# PIRI-MS-S2M.net
KiCad netlist of a schematic drawn in EAGLE
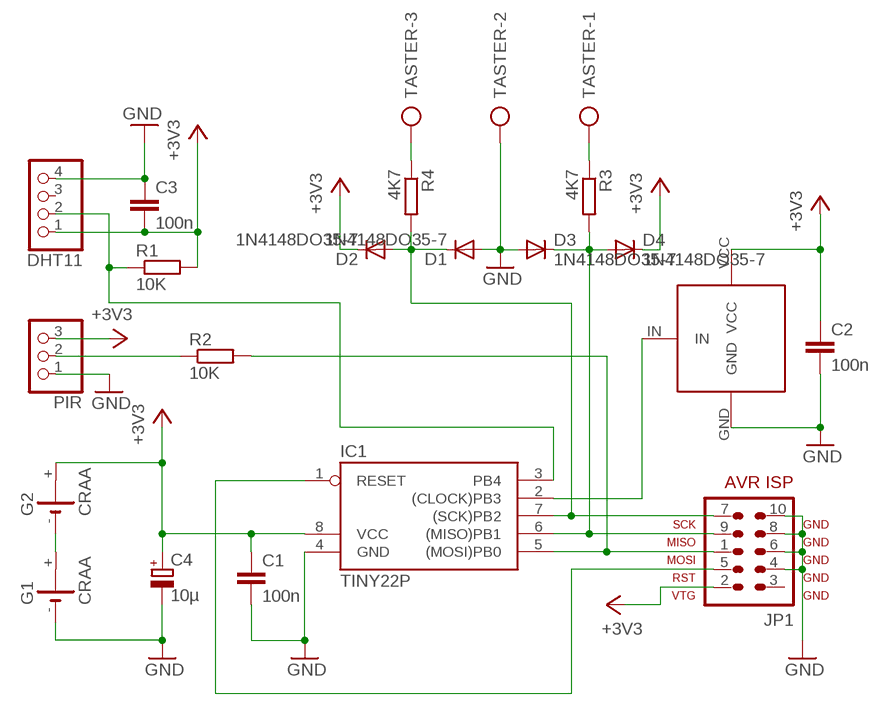
[diagram p0: schematic, sheet 1]

(export (version "E")
  (design (tool "Eeschema 10.0.6"))
  (components
    (comp (ref "C1")
      (value "100n")
      (footprint "eagle-import:C050-024X044")
      (libsource (lib "eagle-import") (part "C-EU050-024X044"))
    )
    (comp (ref "C2")
      (value "100n")
      (footprint "eagle-import:C050-024X044")
      (libsource (lib "eagle-import") (part "C-EU050-024X044"))
    )
    (comp (ref "C3")
      (value "100n")
      (footprint "eagle-import:C050-024X044")
      (libsource (lib "eagle-import") (part "C-EU050-024X044"))
    )
    (comp (ref "C4")
      (value "10µ")
      (footprint "eagle-import:E5-4")
      (libsource (lib "eagle-import") (part "CPOL-EUE5-4"))
    )
    (comp (ref "D1")
      (value "1N4148DO35-7")
      (footprint "eagle-import:DO35-7")
      (libsource (lib "eagle-import") (part "1N4148DO35-7"))
    )
    (comp (ref "D2")
      (value "1N4148DO35-7")
      (footprint "eagle-import:DO35-7")
      (libsource (lib "eagle-import") (part "1N4148DO35-7"))
    )
    (comp (ref "D3")
      (value "1N4148DO35-7")
      (footprint "eagle-import:DO35-7")
      (libsource (lib "eagle-import") (part "1N4148DO35-7"))
    )
    (comp (ref "D4")
      (value "1N4148DO35-7")
      (footprint "eagle-import:DO35-7")
      (libsource (lib "eagle-import") (part "1N4148DO35-7"))
    )
    (comp (ref "DHT11")
      (value "PINHD-1X4")
      (footprint "eagle-import:1X04")
      (libsource (lib "eagle-import") (part "PINHD-1X4"))
    )
    (comp (ref "G1")
      (value "CRAA")
      (footprint "eagle-import:CRAA")
      (libsource (lib "eagle-import") (part "CRAA"))
    )
    (comp (ref "G2")
      (value "CRAA")
      (footprint "eagle-import:CRAA")
      (libsource (lib "eagle-import") (part "CRAA"))
    )
    (comp (ref "IC1")
      (value "TINY22P")
      (footprint "eagle-import:DIL08")
      (libsource (lib "eagle-import") (part "TINY22P"))
    )
    (comp (ref "JP1")
      (value "AVR-ISP-10")
      (footprint "eagle-import:AVR-ISP-10")
      (libsource (lib "eagle-import") (part "AVR-ISP-10"))
    )
    (comp (ref "PIR")
      (value "PINHD-1X3")
      (footprint "eagle-import:1X03")
      (libsource (lib "eagle-import") (part "PINHD-1X3"))
    )
    (comp (ref "R1")
      (value "10K")
      (footprint "eagle-import:0204_7")
      (libsource (lib "eagle-import") (part "R-EU_0204/7"))
    )
    (comp (ref "R2")
      (value "10K")
      (footprint "eagle-import:0204_7")
      (libsource (lib "eagle-import") (part "R-EU_0204/7"))
    )
    (comp (ref "R3")
      (value "4K7")
      (footprint "eagle-import:0204_7")
      (libsource (lib "eagle-import") (part "R-EU_0204/7"))
    )
    (comp (ref "R4")
      (value "4K7")
      (footprint "eagle-import:0204_7")
      (libsource (lib "eagle-import") (part "R-EU_0204/7"))
    )
    (comp (ref "TASTER")
      (value "AK500/3")
      (footprint "eagle-import:AK500_3")
      (libsource (lib "eagle-import") (part "AK500/3"))
    )
    (comp (ref "U$1")
      (value "TX868")
      (footprint "eagle-import:TX868")
      (libsource (lib "eagle-import") (part "TX868"))
    )
  )
  (nets
    (net (code "1") (name "+3V3") (class "Default")
      (node (ref "C1") (pin "1") (pinfunction "1_1") (pintype "passive"))
      (node (ref "C2") (pin "1") (pinfunction "1_1") (pintype "passive"))
      (node (ref "C3") (pin "2") (pinfunction "2_2") (pintype "passive"))
      (node (ref "C4") (pin "+") (pinfunction "+_+") (pintype "passive"))
      (node (ref "D2") (pin "C") (pinfunction "C_C") (pintype "passive"))
      (node (ref "D4") (pin "C") (pinfunction "C_C") (pintype "passive"))
      (node (ref "DHT11") (pin "1") (pinfunction "1_1") (pintype "passive"))
      (node (ref "G2") (pin "+") (pinfunction "+_+") (pintype "passive"))
      (node (ref "IC1") (pin "8") (pinfunction "VCC_8") (pintype "power_in"))
      (node (ref "JP1") (pin "2") (pinfunction "2_2") (pintype "passive"))
      (node (ref "PIR") (pin "3") (pinfunction "3_3") (pintype "passive"))
      (node (ref "R1") (pin "2") (pinfunction "2_2") (pintype "passive"))
      (node (ref "U$1") (pin "VCC") (pinfunction "VCC_VCC") (pintype "power_in"))
    )
    (net (code "2") (name "GND") (class "Default")
      (node (ref "C1") (pin "2") (pinfunction "2_2") (pintype "passive"))
      (node (ref "C2") (pin "2") (pinfunction "2_2") (pintype "passive"))
      (node (ref "C3") (pin "1") (pinfunction "1_1") (pintype "passive"))
      (node (ref "C4") (pin "-") (pinfunction "-_-") (pintype "passive"))
      (node (ref "D1") (pin "A") (pinfunction "A_A") (pintype "passive"))
      (node (ref "D3") (pin "A") (pinfunction "A_A") (pintype "passive"))
      (node (ref "DHT11") (pin "4") (pinfunction "4_4") (pintype "passive"))
      (node (ref "G1") (pin "-") (pinfunction "-_-") (pintype "passive"))
      (node (ref "IC1") (pin "4") (pinfunction "GND_4") (pintype "power_in"))
      (node (ref "JP1") (pin "10") (pinfunction "10_10") (pintype "passive"))
      (node (ref "JP1") (pin "4") (pinfunction "4_4") (pintype "passive"))
      (node (ref "JP1") (pin "6") (pinfunction "6_6") (pintype "passive"))
      (node (ref "JP1") (pin "8") (pinfunction "8_8") (pintype "passive"))
      (node (ref "PIR") (pin "1") (pinfunction "1_1") (pintype "passive"))
      (node (ref "TASTER") (pin "2") (pinfunction "KL_2") (pintype "passive"))
      (node (ref "U$1") (pin "GND") (pinfunction "GND_GND") (pintype "power_in"))
    )
    (net (code "3") (name "Net-(G1-Pad+)") (class "Default")
      (node (ref "G1") (pin "+") (pinfunction "+_+") (pintype "passive"))
      (node (ref "G2") (pin "-") (pinfunction "-_-") (pintype "passive"))
    )
    (net (code "4") (name "Net-(IC1-(CLOCK)PB3)") (class "Default")
      (node (ref "IC1") (pin "2") (pinfunction "(CLOCK)PB3_2") (pintype "bidirectional"))
      (node (ref "U$1") (pin "IN") (pinfunction "IN_IN") (pintype "input"))
    )
    (net (code "5") (name "Net-(IC1-(MISO)PB1)") (class "Default")
      (node (ref "D3") (pin "C") (pinfunction "C_C") (pintype "passive"))
      (node (ref "D4") (pin "A") (pinfunction "A_A") (pintype "passive"))
      (node (ref "IC1") (pin "6") (pinfunction "(MISO)PB1_6") (pintype "bidirectional"))
      (node (ref "JP1") (pin "9") (pinfunction "9_9") (pintype "passive"))
      (node (ref "R3") (pin "2") (pinfunction "2_2") (pintype "passive"))
    )
    (net (code "6") (name "Net-(IC1-(MOSI)PB0)") (class "Default")
      (node (ref "IC1") (pin "5") (pinfunction "(MOSI)PB0_5") (pintype "bidirectional"))
      (node (ref "JP1") (pin "1") (pinfunction "1_1") (pintype "passive"))
      (node (ref "R2") (pin "2") (pinfunction "2_2") (pintype "passive"))
    )
    (net (code "7") (name "Net-(IC1-(SCK)PB2)") (class "Default")
      (node (ref "D1") (pin "C") (pinfunction "C_C") (pintype "passive"))
      (node (ref "D2") (pin "A") (pinfunction "A_A") (pintype "passive"))
      (node (ref "IC1") (pin "7") (pinfunction "(SCK)PB2_7") (pintype "bidirectional"))
      (node (ref "JP1") (pin "7") (pinfunction "7_7") (pintype "passive"))
      (node (ref "R4") (pin "2") (pinfunction "2_2") (pintype "passive"))
    )
    (net (code "8") (name "Net-(IC1-PB4)") (class "Default")
      (node (ref "DHT11") (pin "2") (pinfunction "2_2") (pintype "passive"))
      (node (ref "IC1") (pin "3") (pinfunction "PB4_3") (pintype "bidirectional"))
      (node (ref "R1") (pin "1") (pinfunction "1_1") (pintype "passive"))
    )
    (net (code "9") (name "Net-(IC1-RESET)") (class "Default")
      (node (ref "IC1") (pin "1") (pinfunction "RESET_1") (pintype "input"))
      (node (ref "JP1") (pin "5") (pinfunction "5_5") (pintype "passive"))
    )
    (net (code "10") (name "Net-(PIR-Pad2)") (class "Default")
      (node (ref "PIR") (pin "2") (pinfunction "2_2") (pintype "passive"))
      (node (ref "R2") (pin "1") (pinfunction "1_1") (pintype "passive"))
    )
    (net (code "11") (name "Net-(TASTERA-KL)") (class "Default")
      (node (ref "R3") (pin "1") (pinfunction "1_1") (pintype "passive"))
      (node (ref "TASTER") (pin "1") (pinfunction "KL_1") (pintype "passive"))
    )
    (net (code "12") (name "Net-(TASTERC-KL)") (class "Default")
      (node (ref "R4") (pin "1") (pinfunction "1_1") (pintype "passive"))
      (node (ref "TASTER") (pin "3") (pinfunction "KL_3") (pintype "passive"))
    )
    (net (code "13") (name "unconnected-(DHT11-Pad3)") (class "Default")
      (node (ref "DHT11") (pin "3") (pinfunction "3_3") (pintype "passive"))
    )
    (net (code "14") (name "unconnected-(G1-+-Pad+@1)") (class "Default")
      (node (ref "G1") (pin "+@1") (pinfunction "+_+@1") (pintype "passive"))
    )
    (net (code "15") (name "unconnected-(G2-+-Pad+@1)") (class "Default")
      (node (ref "G2") (pin "+@1") (pinfunction "+_+@1") (pintype "passive"))
    )
    (net (code "16") (name "unconnected-(JP1-Pad3)") (class "Default")
      (node (ref "JP1") (pin "3") (pinfunction "3_3") (pintype "passive"))
    )
  )
)
